# MPU_6050.net
KiCad netlist of a schematic drawn in Altium Designer
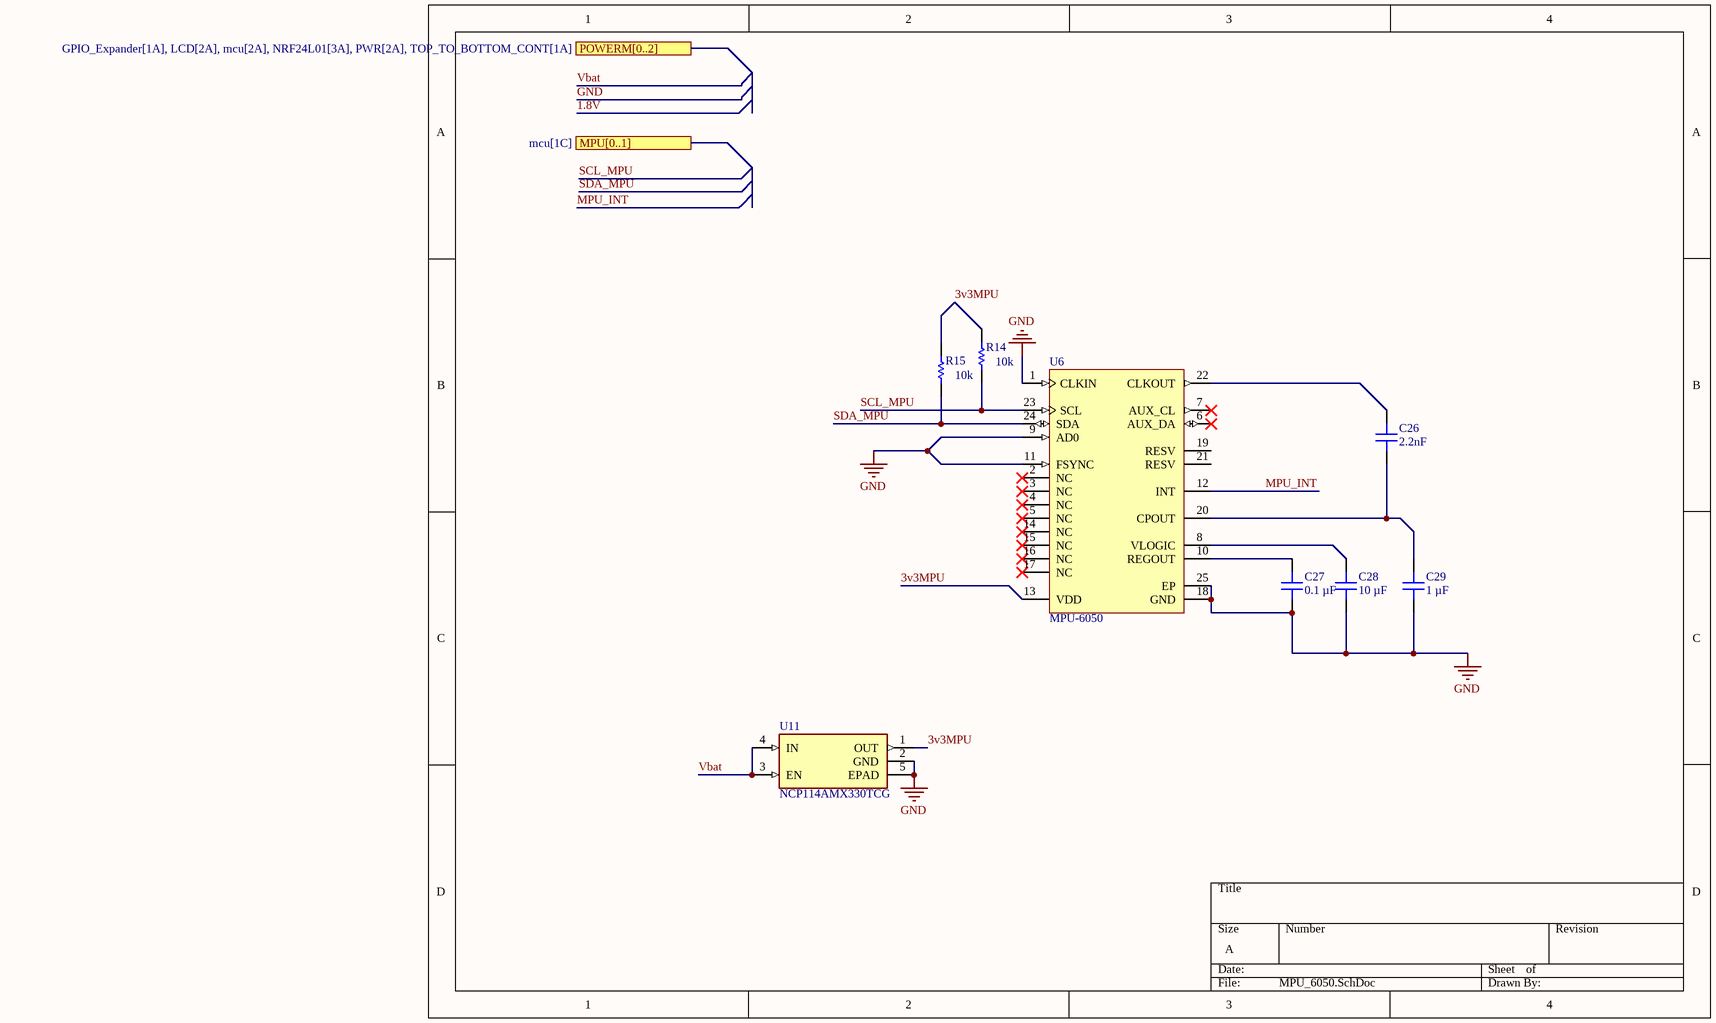
[diagram p0: MPU_6050.SchDoc]

(export (version "E")
  (design (tool "Eeschema 10.0.6"))
  (components
    (comp (ref "C26")
      (value "~")
      (footprint "CAP 0402_1005")
      (description "10V 1uF X5R ±10% 0402 Multilayer Ceramic Capacitors MLCC - SMD/SMT ROHS")
      (fields
        (field (name "CAPACITANCE") "2.2nF")
        (field (name "MANUFACTURER") "Samsung Electro-Mechanics")
        (field (name "MFR.PART #") "CL05A105KP5NNNC")
      )
      (libsource (lib "Celestial Altium Library - altium_library") (part "Capacitor"))
    )
    (comp (ref "C27")
      (value "~")
      (footprint "CAP 0402_1005")
      (description "100nF 16V X7R ±10% 0402 Multilayer Ceramic Capacitors MLCC - SMD/SMT ROHS")
      (fields
        (field (name "CAPACITANCE") "0.1 µF")
        (field (name "MANUFACTURER") "YAGEO")
        (field (name "MFR.PART #") "CC0402KRX7R7BB104")
      )
      (libsource (lib "Celestial Altium Library - altium_library") (part "Capacitor"))
    )
    (comp (ref "C28")
      (value "~")
      (footprint "CAP 0402_1005")
      (description "10V 1uF X5R ±10% 0402 Multilayer Ceramic Capacitors MLCC - SMD/SMT ROHS")
      (fields
        (field (name "CAPACITANCE") "10 µF")
        (field (name "MANUFACTURER") "Samsung Electro-Mechanics")
        (field (name "MFR.PART #") "CL05A106MQ5NUNC")
      )
      (libsource (lib "Celestial Altium Library - altium_library") (part "Capacitor"))
    )
    (comp (ref "C29")
      (value "~")
      (footprint "CAP 0402_1005")
      (description "10V 1uF X5R ±10% 0402 Multilayer Ceramic Capacitors MLCC - SMD/SMT ROHS")
      (fields
        (field (name "CAPACITANCE") "1 µF")
        (field (name "MANUFACTURER") "Samsung Electro-Mechanics")
        (field (name "MFR.PART #") "CL05A105KP5NNNC")
      )
      (libsource (lib "Celestial Altium Library - altium_library") (part "Capacitor"))
    )
    (comp (ref "R14")
      (value "0402WGF1002TCE")
      (footprint "RESC1005X40X25LL05T10")
      (fields
        (field (name "MANUFACTURER") "UNI-ROYAL(Uniroyal Elec)")
        (field (name "JLCPCB PART #") "C25744")
        (field (name "RESISTANCE") "10k")
      )
      (libsource (lib "Altium Content Vault") (part "RES"))
    )
    (comp (ref "R15")
      (value "0402WGF1002TCE")
      (footprint "RESC1005X40X25LL05T10")
      (fields
        (field (name "MANUFACTURER") "UNI-ROYAL(Uniroyal Elec)")
        (field (name "JLCPCB PART #") "C25744")
        (field (name "RESISTANCE") "10k")
      )
      (libsource (lib "Altium Content Vault") (part "RES"))
    )
    (comp (ref "U6")
      (value "MPU-6050")
      (footprint "IS-QFN-24_V")
      (fields (field (name "MANUFACTURER") "TDK InvenSense") (field (name "JLCPCB PART #") "C24112"))
      (libsource (lib "Altium Content Vault") (part "IS-MPU-6050-QFN-24"))
    )
    (comp (ref "U11")
      (value "NCP114AMX330TCG")
      (footprint "REG_NCP114AMX330TCG")
      (description "Linear Voltage Regulator IC Positive Fixed 1 Output 300mA 4-UDFN (1.0x1.0)")
      (fields (field (name "MANUFACTURER") "onsemi") (field (name "JLCPCB PART #") "C133056"))
      (libsource (lib "NCP114AMX330TCG") (part "NCP114AMX330TCG"))
    )
  )
  (nets
    (net (code "7") (name "/3v3MPU") (class "Default")
      (node (ref "R14") (pin "2") (pinfunction "2_2") (pintype "passive"))
      (node (ref "R15") (pin "2") (pinfunction "2_2") (pintype "passive"))
      (node (ref "U11") (pin "1") (pinfunction "OUT_1") (pintype "output"))
      (node (ref "U6") (pin "13") (pinfunction "VDD_13") (pintype "power_in"))
    )
    (net (code "9") (name "/MPU_INT") (class "Default")
      (node (ref "U6") (pin "12") (pinfunction "INT_12") (pintype "open_collector"))
    )
    (net (code "11") (name "/SCL_MPU") (class "Default")
      (node (ref "R14") (pin "1") (pinfunction "1_1") (pintype "passive"))
      (node (ref "U6") (pin "23") (pinfunction "SCL_23") (pintype "input"))
    )
    (net (code "12") (name "/SDA_MPU") (class "Default")
      (node (ref "R15") (pin "1") (pinfunction "1_1") (pintype "passive"))
      (node (ref "U6") (pin "24") (pinfunction "SDA_24") (pintype "bidirectional"))
    )
    (net (code "13") (name "/Vbat") (class "Default")
      (node (ref "U11") (pin "3") (pinfunction "EN_3") (pintype "input"))
      (node (ref "U11") (pin "4") (pinfunction "IN_4") (pintype "input"))
    )
    (net (code "14") (name "GND") (class "Default")
      (node (ref "C27") (pin "1") (pinfunction "1_1") (pintype "passive"))
      (node (ref "C28") (pin "1") (pinfunction "1_1") (pintype "passive"))
      (node (ref "C29") (pin "1") (pinfunction "1_1") (pintype "passive"))
      (node (ref "U11") (pin "2") (pinfunction "GND_2") (pintype "power_in"))
      (node (ref "U11") (pin "5") (pinfunction "EPAD_5") (pintype "passive"))
      (node (ref "U6") (pin "1") (pinfunction "CLKIN_1") (pintype "input"))
      (node (ref "U6") (pin "11") (pinfunction "FSYNC_11") (pintype "input"))
      (node (ref "U6") (pin "18") (pinfunction "GND_18") (pintype "power_in"))
      (node (ref "U6") (pin "25") (pinfunction "EP_25") (pintype "power_in"))
      (node (ref "U6") (pin "9") (pinfunction "AD0_9") (pintype "input"))
    )
    (net (code "15") (name "Net-(U6-CLKOUT)") (class "Default")
      (node (ref "C26") (pin "2") (pinfunction "2_2") (pintype "passive"))
      (node (ref "U6") (pin "22") (pinfunction "CLKOUT_22") (pintype "output"))
    )
    (net (code "16") (name "Net-(U6-CPOUT)") (class "Default")
      (node (ref "C26") (pin "1") (pinfunction "1_1") (pintype "passive"))
      (node (ref "C29") (pin "2") (pinfunction "2_2") (pintype "passive"))
      (node (ref "U6") (pin "20") (pinfunction "CPOUT_20") (pintype "passive"))
    )
    (net (code "17") (name "Net-(U6-REGOUT)") (class "Default")
      (node (ref "C27") (pin "2") (pinfunction "2_2") (pintype "passive"))
      (node (ref "U6") (pin "10") (pinfunction "REGOUT_10") (pintype "passive"))
    )
    (net (code "18") (name "Net-(U6-VLOGIC)") (class "Default")
      (node (ref "C28") (pin "2") (pinfunction "2_2") (pintype "passive"))
      (node (ref "U6") (pin "8") (pinfunction "VLOGIC_8") (pintype "power_in"))
    )
    (net (code "19") (name "unconnected-(U6-AUX_CL-Pad7)") (class "Default")
      (node (ref "U6") (pin "7") (pinfunction "AUX_CL_7") (pintype "output+no_connect"))
    )
    (net (code "20") (name "unconnected-(U6-AUX_DA-Pad6)") (class "Default")
      (node (ref "U6") (pin "6") (pinfunction "AUX_DA_6") (pintype "bidirectional+no_connect"))
    )
    (net (code "21") (name "unconnected-(U6-NC-Pad2)") (class "Default")
      (node (ref "U6") (pin "2") (pinfunction "NC_2") (pintype "passive+no_connect"))
    )
    (net (code "22") (name "unconnected-(U6-NC-Pad3)") (class "Default")
      (node (ref "U6") (pin "3") (pinfunction "NC_3") (pintype "passive+no_connect"))
    )
    (net (code "23") (name "unconnected-(U6-NC-Pad4)") (class "Default")
      (node (ref "U6") (pin "4") (pinfunction "NC_4") (pintype "passive+no_connect"))
    )
    (net (code "24") (name "unconnected-(U6-NC-Pad5)") (class "Default")
      (node (ref "U6") (pin "5") (pinfunction "NC_5") (pintype "passive+no_connect"))
    )
    (net (code "25") (name "unconnected-(U6-NC-Pad14)") (class "Default")
      (node (ref "U6") (pin "14") (pinfunction "NC_14") (pintype "passive+no_connect"))
    )
    (net (code "26") (name "unconnected-(U6-NC-Pad15)") (class "Default")
      (node (ref "U6") (pin "15") (pinfunction "NC_15") (pintype "passive+no_connect"))
    )
    (net (code "27") (name "unconnected-(U6-NC-Pad16)") (class "Default")
      (node (ref "U6") (pin "16") (pinfunction "NC_16") (pintype "passive+no_connect"))
    )
    (net (code "28") (name "unconnected-(U6-NC-Pad17)") (class "Default")
      (node (ref "U6") (pin "17") (pinfunction "NC_17") (pintype "passive+no_connect"))
    )
    (net (code "29") (name "unconnected-(U6-RESV-Pad19)") (class "Default")
      (node (ref "U6") (pin "19") (pinfunction "RESV_19") (pintype "passive"))
    )
    (net (code "30") (name "unconnected-(U6-RESV-Pad21)") (class "Default")
      (node (ref "U6") (pin "21") (pinfunction "RESV_21") (pintype "passive"))
    )
  )
)
